# HV_DC-DC.net
KiCad netlist of a schematic drawn in EAGLE
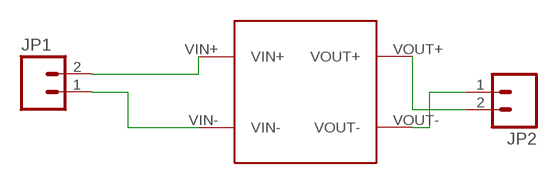
[diagram p0: schematic, sheet 1]

(export (version "E")
  (design (tool "Eeschema 10.0.6"))
  (components
    (comp (ref "JP1")
      (value "M02LOCK")
      (footprint "eagle-import:1X02_LOCK")
      (libsource (lib "eagle-import") (part "M02LOCK"))
    )
    (comp (ref "JP2")
      (value "M02LOCK")
      (footprint "eagle-import:1X02_LOCK")
      (libsource (lib "eagle-import") (part "M02LOCK"))
    )
    (comp (ref "U$1")
      (value "RUW15SL12C")
      (footprint "eagle-import:RUW15SL12C")
      (libsource (lib "eagle-import") (part "RUW15SL12C"))
    )
  )
  (nets
    (net (code "1") (name "Net-(JP1-Pad1)") (class "Default")
      (node (ref "JP1") (pin "1") (pinfunction "1_1") (pintype "passive"))
      (node (ref "U$1") (pin "VIN-") (pinfunction "VIN-_VIN-") (pintype "bidirectional"))
    )
    (net (code "2") (name "Net-(JP1-Pad2)") (class "Default")
      (node (ref "JP1") (pin "2") (pinfunction "2_2") (pintype "passive"))
      (node (ref "U$1") (pin "VIN+") (pinfunction "VIN+_VIN+") (pintype "bidirectional"))
    )
    (net (code "3") (name "Net-(JP2-Pad1)") (class "Default")
      (node (ref "JP2") (pin "1") (pinfunction "1_1") (pintype "passive"))
      (node (ref "U$1") (pin "VOUT-") (pinfunction "VOUT-_VOUT-") (pintype "bidirectional"))
    )
    (net (code "4") (name "Net-(JP2-Pad2)") (class "Default")
      (node (ref "JP2") (pin "2") (pinfunction "2_2") (pintype "passive"))
      (node (ref "U$1") (pin "VOUT+") (pinfunction "VOUT+_VOUT+") (pintype "bidirectional"))
    )
  )
)
